# cansat_Pony_ser_ICSP.net
KiCad netlist of a schematic drawn in EAGLE
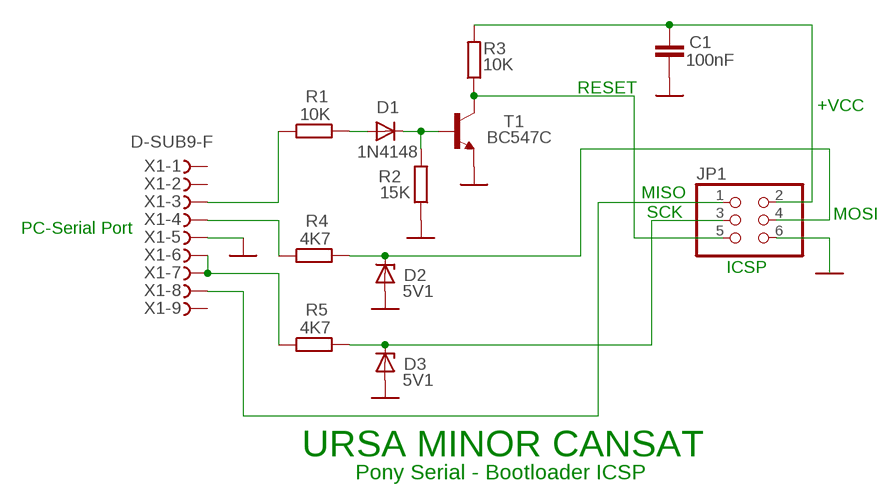
[diagram p0: schematic, sheet 1]

(export (version "E")
  (design (tool "Eeschema 10.0.6"))
  (components
    (comp (ref "C1")
      (value "100nF")
      (footprint "eagle-import:C2.5-2")
      (libsource (lib "eagle-import") (part "C2.5/2"))
    )
    (comp (ref "D1")
      (value "1N4148")
      (footprint "eagle-import:DO35-10")
      (libsource (lib "eagle-import") (part "1N4148DO35-10"))
    )
    (comp (ref "D2")
      (value "5V1")
      (footprint "eagle-import:SOD81")
      (libsource (lib "eagle-import") (part "BZD23"))
    )
    (comp (ref "D3")
      (value "5V1")
      (footprint "eagle-import:SOD81")
      (libsource (lib "eagle-import") (part "BZD23"))
    )
    (comp (ref "JP1")
      (value "PINHD-2X3")
      (footprint "eagle-import:2X03")
      (libsource (lib "eagle-import") (part "PINHD-2X3"))
    )
    (comp (ref "R1")
      (value "10K")
      (footprint "eagle-import:0204V")
      (libsource (lib "eagle-import") (part "R-EU_0204_2V"))
    )
    (comp (ref "R2")
      (value "15K")
      (footprint "eagle-import:0204V")
      (libsource (lib "eagle-import") (part "R-EU_0204_2V"))
    )
    (comp (ref "R3")
      (value "10K")
      (footprint "eagle-import:0204V")
      (libsource (lib "eagle-import") (part "R-EU_0204_2V"))
    )
    (comp (ref "R4")
      (value "4K7")
      (footprint "eagle-import:0204V")
      (libsource (lib "eagle-import") (part "R-EU_0204_2V"))
    )
    (comp (ref "R5")
      (value "4K7")
      (footprint "eagle-import:0204V")
      (libsource (lib "eagle-import") (part "R-EU_0204_2V"))
    )
    (comp (ref "T1")
      (value "BC547C")
      (footprint "eagle-import:TO92-CBE")
      (libsource (lib "eagle-import") (part "-NPN-TO92-CBEBC547B"))
    )
    (comp (ref "X1")
      (value "D-SUB9-F")
      (footprint "eagle-import:H2M09RA")
      (libsource (lib "eagle-import") (part "D-SUB9-H2M09RA"))
    )
  )
  (nets
    (net (code "1") (name "GND") (class "Default")
      (node (ref "C1") (pin "2") (pinfunction "2_2") (pintype "passive"))
      (node (ref "D2") (pin "A") (pinfunction "A_A") (pintype "passive"))
      (node (ref "D3") (pin "A") (pinfunction "A_A") (pintype "passive"))
      (node (ref "R2") (pin "1") (pinfunction "1_1") (pintype "passive"))
      (node (ref "T1") (pin "E") (pinfunction "E_E") (pintype "passive"))
      (node (ref "X1") (pin "5") (pinfunction "F_5") (pintype "passive"))
    )
    (net (code "2") (name "Net-(C1-Pad1)") (class "Default")
      (node (ref "C1") (pin "1") (pinfunction "1_1") (pintype "passive"))
      (node (ref "JP1") (pin "2") (pinfunction "2_2") (pintype "passive"))
      (node (ref "R3") (pin "2") (pinfunction "2_2") (pintype "passive"))
    )
    (net (code "3") (name "Net-(D1-PadA)") (class "Default")
      (node (ref "D1") (pin "A") (pinfunction "A_A") (pintype "passive"))
      (node (ref "R1") (pin "2") (pinfunction "2_2") (pintype "passive"))
    )
    (net (code "4") (name "Net-(D1-PadC)") (class "Default")
      (node (ref "D1") (pin "C") (pinfunction "C_C") (pintype "passive"))
      (node (ref "R2") (pin "2") (pinfunction "2_2") (pintype "passive"))
      (node (ref "T1") (pin "B") (pinfunction "B_B") (pintype "passive"))
    )
    (net (code "5") (name "Net-(D2-PadC)") (class "Default")
      (node (ref "D2") (pin "C") (pinfunction "C_C") (pintype "passive"))
      (node (ref "JP1") (pin "4") (pinfunction "4_4") (pintype "passive"))
      (node (ref "R4") (pin "2") (pinfunction "2_2") (pintype "passive"))
    )
    (net (code "6") (name "Net-(D3-PadC)") (class "Default")
      (node (ref "D3") (pin "C") (pinfunction "C_C") (pintype "passive"))
      (node (ref "JP1") (pin "3") (pinfunction "3_3") (pintype "passive"))
      (node (ref "R5") (pin "2") (pinfunction "2_2") (pintype "passive"))
    )
    (net (code "7") (name "Net-(JP1-Pad5)") (class "Default")
      (node (ref "JP1") (pin "5") (pinfunction "5_5") (pintype "passive"))
      (node (ref "R3") (pin "1") (pinfunction "1_1") (pintype "passive"))
      (node (ref "T1") (pin "C") (pinfunction "C_C") (pintype "passive"))
    )
    (net (code "8") (name "Net-(X1C-F)") (class "Default")
      (node (ref "R1") (pin "1") (pinfunction "1_1") (pintype "passive"))
      (node (ref "X1") (pin "3") (pinfunction "F_3") (pintype "passive"))
    )
    (net (code "9") (name "Net-(X1D-F)") (class "Default")
      (node (ref "R4") (pin "1") (pinfunction "1_1") (pintype "passive"))
      (node (ref "X1") (pin "4") (pinfunction "F_4") (pintype "passive"))
    )
    (net (code "10") (name "Net-(X1F-F)") (class "Default")
      (node (ref "R5") (pin "1") (pinfunction "1_1") (pintype "passive"))
      (node (ref "X1") (pin "6") (pinfunction "F_6") (pintype "passive"))
      (node (ref "X1") (pin "7") (pinfunction "F_7") (pintype "passive"))
    )
    (net (code "11") (name "Net-(X1H-F)") (class "Default")
      (node (ref "JP1") (pin "1") (pinfunction "1_1") (pintype "passive"))
      (node (ref "X1") (pin "8") (pinfunction "F_8") (pintype "passive"))
    )
    (net (code "12") (name "unconnected-(JP1-Pad6)") (class "Default")
      (node (ref "JP1") (pin "6") (pinfunction "6_6") (pintype "passive"))
    )
    (net (code "13") (name "unconnected-(X1A-F-Pad1)") (class "Default")
      (node (ref "X1") (pin "1") (pinfunction "F_1") (pintype "passive"))
    )
    (net (code "14") (name "unconnected-(X1B-F-Pad2)") (class "Default")
      (node (ref "X1") (pin "2") (pinfunction "F_2") (pintype "passive"))
    )
    (net (code "15") (name "unconnected-(X1I-F-Pad9)") (class "Default")
      (node (ref "X1") (pin "9") (pinfunction "F_9") (pintype "passive"))
    )
  )
)
